# DAU_Kupplung_3phasig_V1_11.net
KiCad netlist of a schematic drawn in EAGLE
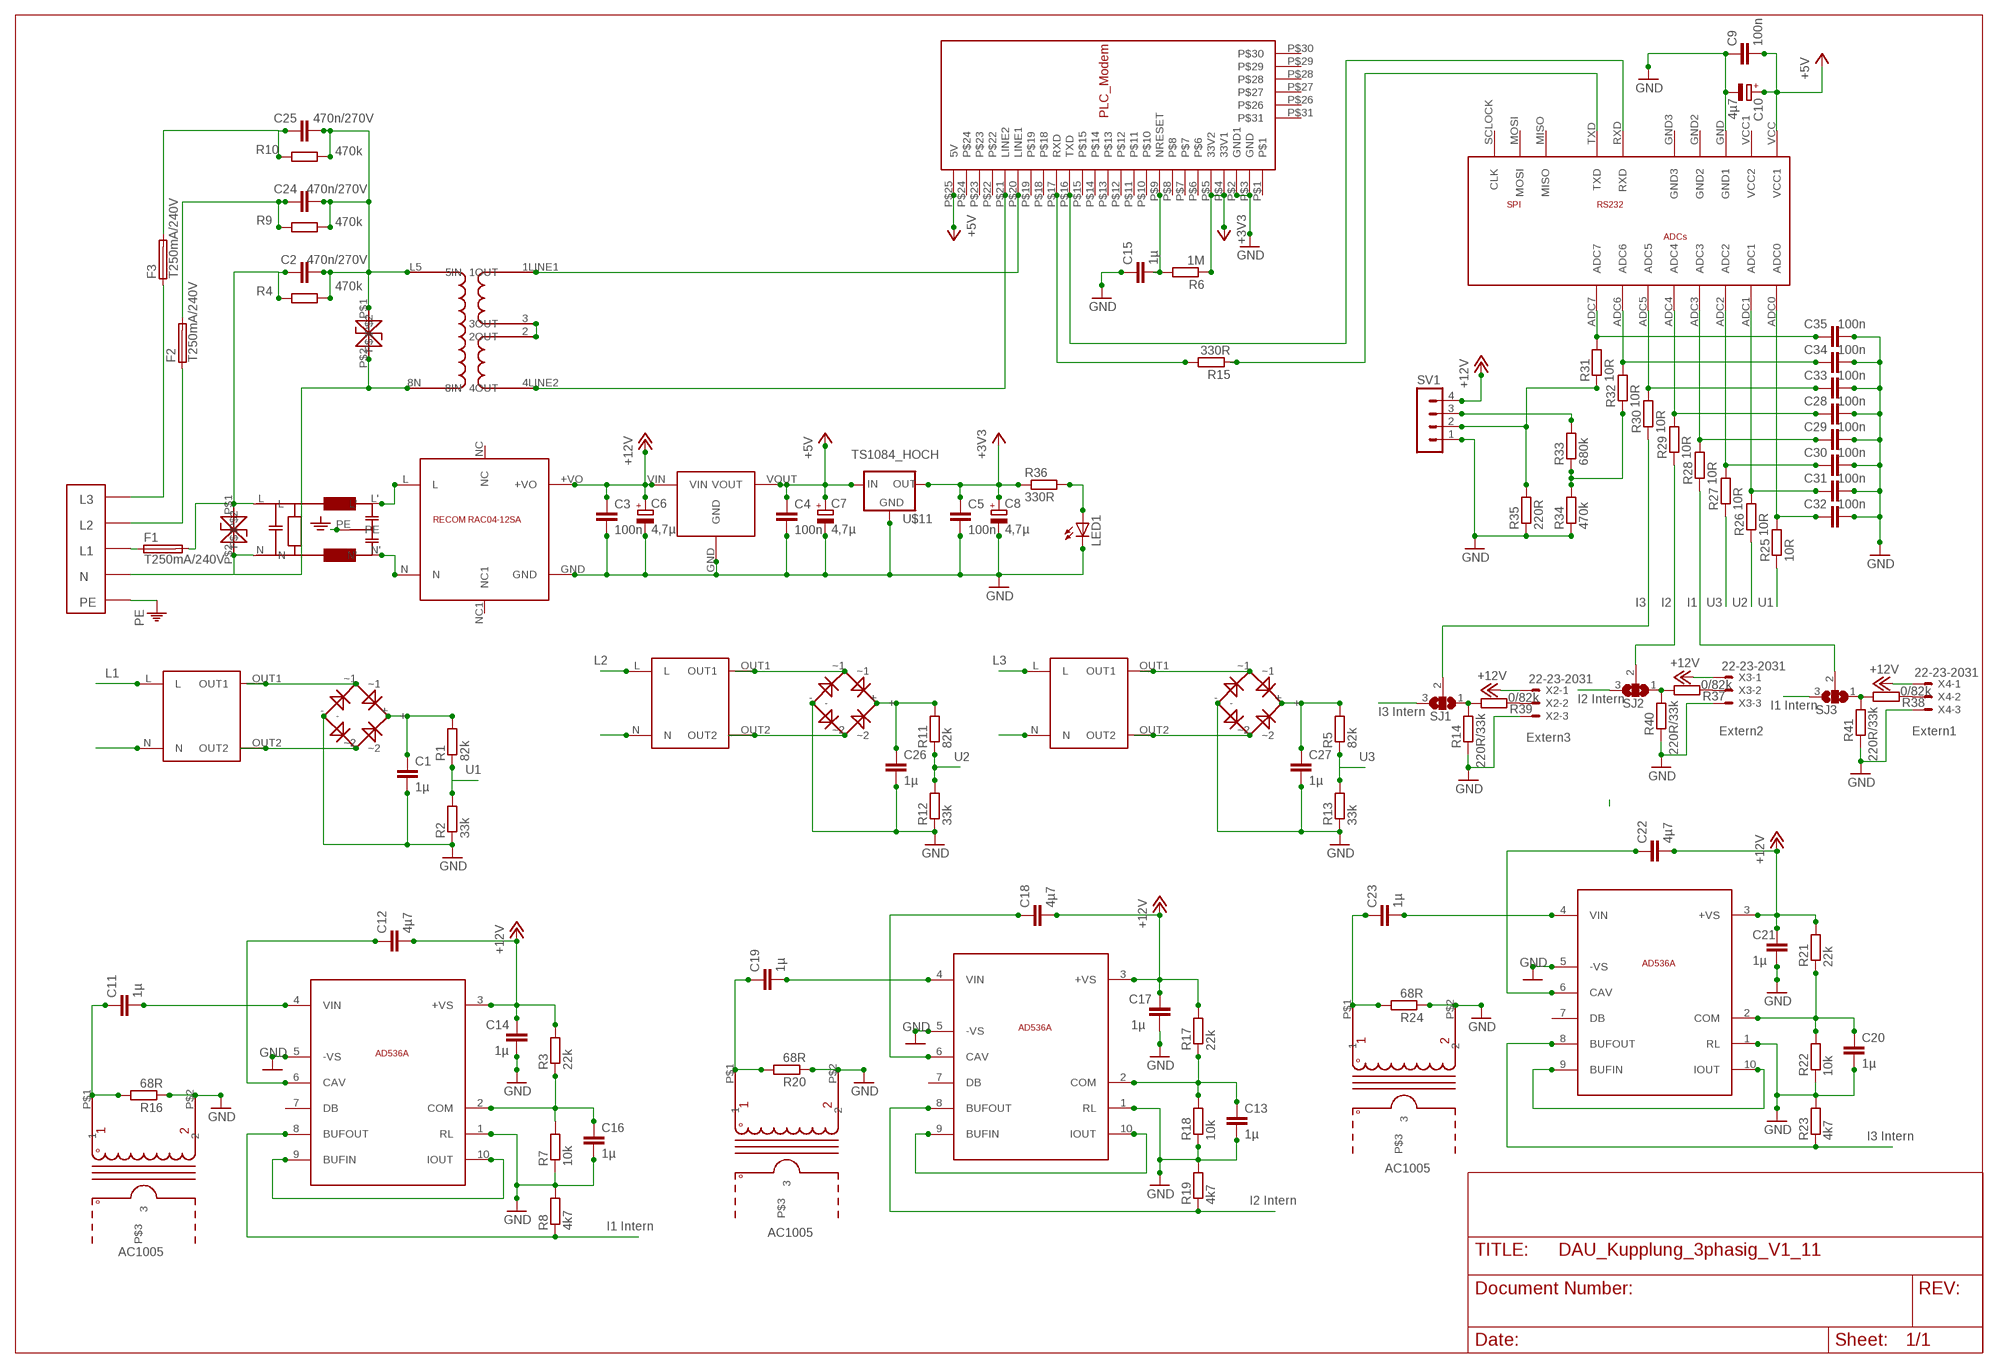
[diagram p0: schematic, sheet 1]

(export (version "E")
  (design (tool "Eeschema 10.0.6"))
  (components
    (comp (ref "AC1002_1")
      (value "AC1010")
      (footprint "eagle-import:AC1010")
      (libsource (lib "eagle-import") (part "AC1010"))
    )
    (comp (ref "C1")
      (value "1µ")
      (footprint "eagle-import:C0805K")
      (libsource (lib "eagle-import") (part "C-EUC0805K"))
    )
    (comp (ref "C2")
      (value "470n/270V")
      (footprint "eagle-import:C225-087X268")
      (libsource (lib "eagle-import") (part "C-EU225-087X268"))
    )
    (comp (ref "C3")
      (value "100n")
      (footprint "eagle-import:C0805K")
      (libsource (lib "eagle-import") (part "C-EUC0805K"))
    )
    (comp (ref "C4")
      (value "100n")
      (footprint "eagle-import:C0805K")
      (libsource (lib "eagle-import") (part "C-EUC0805K"))
    )
    (comp (ref "C5")
      (value "100n")
      (footprint "eagle-import:C0805K")
      (libsource (lib "eagle-import") (part "C-EUC0805K"))
    )
    (comp (ref "C6")
      (value "4,7µ")
      (footprint "eagle-import:E2,5-6")
      (libsource (lib "eagle-import") (part "resistor_CPOL-EUE2.5-6"))
    )
    (comp (ref "C7")
      (value "4,7µ")
      (footprint "eagle-import:E2,5-6")
      (libsource (lib "eagle-import") (part "resistor_CPOL-EUE2.5-6"))
    )
    (comp (ref "C8")
      (value "4,7µ")
      (footprint "eagle-import:E2,5-6")
      (libsource (lib "eagle-import") (part "resistor_CPOL-EUE2.5-6"))
    )
    (comp (ref "C9")
      (value "100n")
      (footprint "eagle-import:C0805K")
      (libsource (lib "eagle-import") (part "C-EUC0805K"))
    )
    (comp (ref "C10")
      (value "4µ7")
      (footprint "eagle-import:E2,5-6E")
      (libsource (lib "eagle-import") (part "CPOL-EUE2,5-6E"))
    )
    (comp (ref "C11")
      (value "1µ")
      (footprint "eagle-import:C0805K")
      (libsource (lib "eagle-import") (part "C-EUC0805K"))
    )
    (comp (ref "C12")
      (value "4µ7")
      (footprint "eagle-import:C0805K")
      (libsource (lib "eagle-import") (part "C-EUC0805K"))
    )
    (comp (ref "C13")
      (value "1µ")
      (footprint "eagle-import:C0805K")
      (libsource (lib "eagle-import") (part "C-EUC0805K"))
    )
    (comp (ref "C14")
      (value "1µ")
      (footprint "eagle-import:C0805K")
      (libsource (lib "eagle-import") (part "C-EUC0805K"))
    )
    (comp (ref "C15")
      (value "1µ")
      (footprint "eagle-import:C0805K")
      (libsource (lib "eagle-import") (part "C-EUC0805K"))
    )
    (comp (ref "C16")
      (value "1µ")
      (footprint "eagle-import:C0805K")
      (libsource (lib "eagle-import") (part "C-EUC0805K"))
    )
    (comp (ref "C17")
      (value "1µ")
      (footprint "eagle-import:C0805K")
      (libsource (lib "eagle-import") (part "C-EUC0805K"))
    )
    (comp (ref "C18")
      (value "4µ7")
      (footprint "eagle-import:C0805K")
      (libsource (lib "eagle-import") (part "C-EUC0805K"))
    )
    (comp (ref "C19")
      (value "1µ")
      (footprint "eagle-import:C0805K")
      (libsource (lib "eagle-import") (part "C-EUC0805K"))
    )
    (comp (ref "C20")
      (value "1µ")
      (footprint "eagle-import:C0805K")
      (libsource (lib "eagle-import") (part "C-EUC0805K"))
    )
    (comp (ref "C21")
      (value "1µ")
      (footprint "eagle-import:C0805K")
      (libsource (lib "eagle-import") (part "C-EUC0805K"))
    )
    (comp (ref "C22")
      (value "4µ7")
      (footprint "eagle-import:C0805K")
      (libsource (lib "eagle-import") (part "C-EUC0805K"))
    )
    (comp (ref "C23")
      (value "1µ")
      (footprint "eagle-import:C0805K")
      (libsource (lib "eagle-import") (part "C-EUC0805K"))
    )
    (comp (ref "C24")
      (value "470n/270V")
      (footprint "eagle-import:C225-087X268")
      (libsource (lib "eagle-import") (part "C-EU225-087X268"))
    )
    (comp (ref "C25")
      (value "470n/270V")
      (footprint "eagle-import:C225-087X268")
      (libsource (lib "eagle-import") (part "C-EU225-087X268"))
    )
    (comp (ref "C26")
      (value "1µ")
      (footprint "eagle-import:C0805K")
      (libsource (lib "eagle-import") (part "C-EUC0805K"))
    )
    (comp (ref "C27")
      (value "1µ")
      (footprint "eagle-import:C0805K")
      (libsource (lib "eagle-import") (part "C-EUC0805K"))
    )
    (comp (ref "C28")
      (value "100n")
      (footprint "eagle-import:C0805K")
      (libsource (lib "eagle-import") (part "C-EUC0805K"))
    )
    (comp (ref "C29")
      (value "100n")
      (footprint "eagle-import:C0805K")
      (libsource (lib "eagle-import") (part "C-EUC0805K"))
    )
    (comp (ref "C30")
      (value "100n")
      (footprint "eagle-import:C0805K")
      (libsource (lib "eagle-import") (part "C-EUC0805K"))
    )
    (comp (ref "C31")
      (value "100n")
      (footprint "eagle-import:C0805K")
      (libsource (lib "eagle-import") (part "C-EUC0805K"))
    )
    (comp (ref "C32")
      (value "100n")
      (footprint "eagle-import:C0805K")
      (libsource (lib "eagle-import") (part "C-EUC0805K"))
    )
    (comp (ref "C33")
      (value "100n")
      (footprint "eagle-import:C0805K")
      (libsource (lib "eagle-import") (part "C-EUC0805K"))
    )
    (comp (ref "C34")
      (value "100n")
      (footprint "eagle-import:C0805K")
      (libsource (lib "eagle-import") (part "C-EUC0805K"))
    )
    (comp (ref "C35")
      (value "100n")
      (footprint "eagle-import:C0805K")
      (libsource (lib "eagle-import") (part "C-EUC0805K"))
    )
    (comp (ref "F1")
      (value "T250mA/240V")
      (footprint "eagle-import:TR5")
      (libsource (lib "eagle-import") (part "TR5"))
    )
    (comp (ref "F2")
      (value "T250mA/240V")
      (footprint "eagle-import:TR5")
      (fields (field (name "OC_FARNELL") "unknown") (field (name "OC_NEWARK") "unknown"))
      (libsource (lib "eagle-import") (part "TR5"))
    )
    (comp (ref "F3")
      (value "T250mA/240V")
      (footprint "eagle-import:TR5")
      (fields (field (name "OC_FARNELL") "unknown") (field (name "OC_NEWARK") "unknown"))
      (libsource (lib "eagle-import") (part "TR5"))
    )
    (comp (ref "LED1")
      (value "LEDSQR2X5")
      (footprint "eagle-import:LED2X5")
      (libsource (lib "eagle-import") (part "LEDSQR2X5"))
    )
    (comp (ref "P6KE300CA")
      (value "P6KE300CA")
      (footprint "eagle-import:TSV")
      (libsource (lib "eagle-import") (part "TSV"))
    )
    (comp (ref "R1")
      (value "82k")
      (footprint "eagle-import:R0805")
      (libsource (lib "eagle-import") (part "R-EU_R0805"))
    )
    (comp (ref "R2")
      (value "33k")
      (footprint "eagle-import:R0805")
      (libsource (lib "eagle-import") (part "R-EU_R0805"))
    )
    (comp (ref "R3")
      (value "22k")
      (footprint "eagle-import:R0805")
      (libsource (lib "eagle-import") (part "R-EU_R0805"))
    )
    (comp (ref "R4")
      (value "470k")
      (footprint "eagle-import:0204_7")
      (libsource (lib "eagle-import") (part "R-EU_0204/7"))
    )
    (comp (ref "R5")
      (value "82k")
      (footprint "eagle-import:R0805")
      (libsource (lib "eagle-import") (part "R-EU_R0805"))
    )
    (comp (ref "R6")
      (value "1M")
      (footprint "eagle-import:R0805")
      (libsource (lib "eagle-import") (part "R-EU_R0805"))
    )
    (comp (ref "R7")
      (value "10k")
      (footprint "eagle-import:R0805")
      (libsource (lib "eagle-import") (part "R-EU_R0805"))
    )
    (comp (ref "R8")
      (value "4k7")
      (footprint "eagle-import:R0805")
      (libsource (lib "eagle-import") (part "R-EU_R0805"))
    )
    (comp (ref "R9")
      (value "470k")
      (footprint "eagle-import:0204_7")
      (libsource (lib "eagle-import") (part "R-EU_0204/7"))
    )
    (comp (ref "R10")
      (value "470k")
      (footprint "eagle-import:0204_7")
      (libsource (lib "eagle-import") (part "R-EU_0204/7"))
    )
    (comp (ref "R11")
      (value "82k")
      (footprint "eagle-import:R0805")
      (libsource (lib "eagle-import") (part "R-EU_R0805"))
    )
    (comp (ref "R12")
      (value "33k")
      (footprint "eagle-import:R0805")
      (libsource (lib "eagle-import") (part "R-EU_R0805"))
    )
    (comp (ref "R13")
      (value "33k")
      (footprint "eagle-import:R0805")
      (libsource (lib "eagle-import") (part "R-EU_R0805"))
    )
    (comp (ref "R14")
      (value "220R/33k")
      (footprint "eagle-import:R0805")
      (libsource (lib "eagle-import") (part "R-EU_R0805"))
    )
    (comp (ref "R15")
      (value "330R")
      (footprint "eagle-import:R0805")
      (libsource (lib "eagle-import") (part "R-EU_R0805"))
    )
    (comp (ref "R16")
      (value "68R")
      (footprint "eagle-import:0204_7")
      (libsource (lib "eagle-import") (part "R-EU_0204/7"))
    )
    (comp (ref "R17")
      (value "22k")
      (footprint "eagle-import:R0805")
      (libsource (lib "eagle-import") (part "R-EU_R0805"))
    )
    (comp (ref "R18")
      (value "10k")
      (footprint "eagle-import:R0805")
      (libsource (lib "eagle-import") (part "R-EU_R0805"))
    )
    (comp (ref "R19")
      (value "4k7")
      (footprint "eagle-import:R0805")
      (libsource (lib "eagle-import") (part "R-EU_R0805"))
    )
    (comp (ref "R20")
      (value "68R")
      (footprint "eagle-import:0204_7")
      (libsource (lib "eagle-import") (part "R-EU_0204/7"))
    )
    (comp (ref "R21")
      (value "22k")
      (footprint "eagle-import:R0805")
      (libsource (lib "eagle-import") (part "R-EU_R0805"))
    )
    (comp (ref "R22")
      (value "10k")
      (footprint "eagle-import:R0805")
      (libsource (lib "eagle-import") (part "R-EU_R0805"))
    )
    (comp (ref "R23")
      (value "4k7")
      (footprint "eagle-import:R0805")
      (libsource (lib "eagle-import") (part "R-EU_R0805"))
    )
    (comp (ref "R24")
      (value "68R")
      (footprint "eagle-import:0204_7")
      (libsource (lib "eagle-import") (part "R-EU_0204/7"))
    )
    (comp (ref "R25")
      (value "10R")
      (footprint "eagle-import:R0805")
      (libsource (lib "eagle-import") (part "R-EU_R0805"))
    )
    (comp (ref "R26")
      (value "10R")
      (footprint "eagle-import:R0805")
      (libsource (lib "eagle-import") (part "R-EU_R0805"))
    )
    (comp (ref "R27")
      (value "10R")
      (footprint "eagle-import:R0805")
      (libsource (lib "eagle-import") (part "R-EU_R0805"))
    )
    (comp (ref "R28")
      (value "10R")
      (footprint "eagle-import:R0805")
      (libsource (lib "eagle-import") (part "R-EU_R0805"))
    )
    (comp (ref "R29")
      (value "10R")
      (footprint "eagle-import:R0805")
      (libsource (lib "eagle-import") (part "R-EU_R0805"))
    )
    (comp (ref "R30")
      (value "10R")
      (footprint "eagle-import:R0805")
      (libsource (lib "eagle-import") (part "R-EU_R0805"))
    )
    (comp (ref "R31")
      (value "10R")
      (footprint "eagle-import:R0805")
      (libsource (lib "eagle-import") (part "R-EU_R0805"))
    )
    (comp (ref "R32")
      (value "10R")
      (footprint "eagle-import:R0805")
      (libsource (lib "eagle-import") (part "R-EU_R0805"))
    )
    (comp (ref "R33")
      (value "680k")
      (footprint "eagle-import:R0805")
      (libsource (lib "eagle-import") (part "R-EU_R0805"))
    )
    (comp (ref "R34")
      (value "470k")
      (footprint "eagle-import:R0805")
      (libsource (lib "eagle-import") (part "R-EU_R0805"))
    )
    (comp (ref "R35")
      (value "220R")
      (footprint "eagle-import:R0805")
      (libsource (lib "eagle-import") (part "R-EU_R0805"))
    )
    (comp (ref "R36")
      (value "330R")
      (footprint "eagle-import:R0805")
      (libsource (lib "eagle-import") (part "R-EU_R0805"))
    )
    (comp (ref "R37")
      (value "0/82k")
      (footprint "eagle-import:R0805")
      (libsource (lib "eagle-import") (part "R-EU_R0805"))
    )
    (comp (ref "R38")
      (value "0/82k")
      (footprint "eagle-import:R0805")
      (libsource (lib "eagle-import") (part "R-EU_R0805"))
    )
    (comp (ref "R39")
      (value "0/82k")
      (footprint "eagle-import:R0805")
      (libsource (lib "eagle-import") (part "R-EU_R0805"))
    )
    (comp (ref "R40")
      (value "220R/33k")
      (footprint "eagle-import:R0805")
      (libsource (lib "eagle-import") (part "R-EU_R0805"))
    )
    (comp (ref "R41")
      (value "220R/33k")
      (footprint "eagle-import:R0805")
      (libsource (lib "eagle-import") (part "R-EU_R0805"))
    )
    (comp (ref "SJ1")
      (value "SJ2WW")
      (footprint "eagle-import:SJ_2W")
      (libsource (lib "eagle-import") (part "SJ2WW"))
    )
    (comp (ref "SJ2")
      (value "SJ2WW")
      (footprint "eagle-import:SJ_2W")
      (libsource (lib "eagle-import") (part "SJ2WW"))
    )
    (comp (ref "SJ3")
      (value "SJ2WW")
      (footprint "eagle-import:SJ_2W")
      (libsource (lib "eagle-import") (part "SJ2WW"))
    )
    (comp (ref "SV1")
      (value "MA04-1")
      (footprint "eagle-import:MA04-1")
      (libsource (lib "eagle-import") (part "MA04-1"))
    )
    (comp (ref "TSV2")
      (value "TSV")
      (footprint "eagle-import:TSV")
      (libsource (lib "eagle-import") (part "TSV"))
    )
    (comp (ref "U$1")
      (value "RECOM_RAC04_12SA")
      (footprint "eagle-import:RAC04_12SA")
      (libsource (lib "eagle-import") (part "RECOM_RAC04_12SA"))
    )
    (comp (ref "U$2")
      (value "SICHERHEITSTRAFO")
      (footprint "eagle-import:TRAFO_0,35VA")
      (libsource (lib "eagle-import") (part "SICHERHEITSTRAFO"))
    )
    (comp (ref "U$3")
      (value "ADUC831_MINIMUM")
      (footprint "eagle-import:ADUC_MINIMUM")
      (libsource (lib "eagle-import") (part "ADUC831_MINIMUM"))
    )
    (comp (ref "U$4")
      (value "MODEMSTECKER")
      (footprint "eagle-import:MODEM_FUSS")
      (libsource (lib "eagle-import") (part "MODEMSTECKER"))
    )
    (comp (ref "U$5")
      (value "PLC_UEBERTRAGER_V2")
      (footprint "eagle-import:PLC-UEBERTRAGER_V2")
      (libsource (lib "eagle-import") (part "PLC_UEBERTRAGER_V2"))
    )
    (comp (ref "U$7")
      (value "AC1010")
      (footprint "eagle-import:AC1010")
      (libsource (lib "eagle-import") (part "AC1010"))
    )
    (comp (ref "U$8")
      (value "RECTIFIER")
      (footprint "eagle-import:RECTIFIER")
      (libsource (lib "eagle-import") (part "RECTIFIER"))
    )
    (comp (ref "U$10")
      (value "RECOM_785_05")
      (footprint "eagle-import:RECOM785X")
      (libsource (lib "eagle-import") (part "RECOM_785_05"))
    )
    (comp (ref "U$11")
      (value "TS1084_HOCH")
      (footprint "eagle-import:TS1084_HOCH")
      (libsource (lib "eagle-import") (part "TS1084_HOCH"))
    )
    (comp (ref "U$12")
      (value "AD536")
      (footprint "eagle-import:TO100_10PIN")
      (libsource (lib "eagle-import") (part "AD536"))
    )
    (comp (ref "U$13")
      (value "AD536")
      (footprint "eagle-import:TO100_10PIN")
      (libsource (lib "eagle-import") (part "AD536"))
    )
    (comp (ref "U$14")
      (value "AC1010")
      (footprint "eagle-import:AC1010")
      (libsource (lib "eagle-import") (part "AC1010"))
    )
    (comp (ref "U$15")
      (value "AD536")
      (footprint "eagle-import:TO100_10PIN")
      (libsource (lib "eagle-import") (part "AD536"))
    )
    (comp (ref "U$16")
      (value "SICHERHEITSTRAFO")
      (footprint "eagle-import:TRAFO_0,35VA")
      (libsource (lib "eagle-import") (part "SICHERHEITSTRAFO"))
    )
    (comp (ref "U$17")
      (value "RECTIFIER")
      (footprint "eagle-import:RECTIFIER")
      (libsource (lib "eagle-import") (part "RECTIFIER"))
    )
    (comp (ref "U$18")
      (value "SICHERHEITSTRAFO")
      (footprint "eagle-import:TRAFO_0,35VA")
      (libsource (lib "eagle-import") (part "SICHERHEITSTRAFO"))
    )
    (comp (ref "U$19")
      (value "RECTIFIER")
      (footprint "eagle-import:RECTIFIER")
      (libsource (lib "eagle-import") (part "RECTIFIER"))
    )
    (comp (ref "U$20")
      (value "NETZFILTER_05_A")
      (footprint "eagle-import:NETZFILTER")
      (libsource (lib "eagle-import") (part "NETZFILTER_05_A"))
    )
    (comp (ref "X1")
      (value "CONNECTO_5_POL")
      (footprint "eagle-import:CONNECTOR_5_POL")
      (libsource (lib "eagle-import") (part "CONNECTO_5_POL"))
    )
    (comp (ref "X2")
      (value "22-23-2031")
      (footprint "eagle-import:22-23-2031")
      (fields (field (name "MF") "MOLEX"))
      (libsource (lib "eagle-import") (part "22-23-2031"))
    )
    (comp (ref "X3")
      (value "22-23-2031")
      (footprint "eagle-import:22-23-2031")
      (fields (field (name "MF") "MOLEX"))
      (libsource (lib "eagle-import") (part "22-23-2031"))
    )
    (comp (ref "X4")
      (value "22-23-2031")
      (footprint "eagle-import:22-23-2031")
      (fields (field (name "MF") "MOLEX"))
      (libsource (lib "eagle-import") (part "22-23-2031"))
    )
  )
  (nets
    (net (code "1") (name "+3V3") (class "Default")
      (node (ref "C5") (pin "1") (pinfunction "1_1") (pintype "passive"))
      (node (ref "C8") (pin "+") (pinfunction "+_+") (pintype "passive"))
      (node (ref "R36") (pin "1") (pinfunction "1_1") (pintype "passive"))
      (node (ref "R6") (pin "1") (pinfunction "1_1") (pintype "passive"))
      (node (ref "U$11") (pin "OUT") (pinfunction "OUT_OUT") (pintype "passive"))
      (node (ref "U$4") (pin "P$4") (pinfunction "33V1_P$4") (pintype "bidirectional"))
      (node (ref "U$4") (pin "P$5") (pinfunction "33V2_P$5") (pintype "bidirectional"))
    )
    (net (code "2") (name "+5V") (class "Default")
      (node (ref "C10") (pin "+") (pinfunction "+_+") (pintype "passive"))
      (node (ref "C4") (pin "1") (pinfunction "1_1") (pintype "passive"))
      (node (ref "C7") (pin "+") (pinfunction "+_+") (pintype "passive"))
      (node (ref "C9") (pin "2") (pinfunction "2_2") (pintype "passive"))
      (node (ref "U$10") (pin "VOUT") (pinfunction "VOUT_VOUT") (pintype "bidirectional"))
      (node (ref "U$11") (pin "IN") (pinfunction "IN_IN") (pintype "input"))
      (node (ref "U$3") (pin "VCC") (pinfunction "VCC1_VCC") (pintype "bidirectional"))
      (node (ref "U$4") (pin "P$25") (pinfunction "5V_P$25") (pintype "bidirectional"))
    )
    (net (code "3") (name "+12V") (class "Default")
      (node (ref "C12") (pin "2") (pinfunction "2_2") (pintype "passive"))
      (node (ref "C14") (pin "2") (pinfunction "2_2") (pintype "passive"))
      (node (ref "C17") (pin "2") (pinfunction "2_2") (pintype "passive"))
      (node (ref "C18") (pin "2") (pinfunction "2_2") (pintype "passive"))
      (node (ref "C21") (pin "1") (pinfunction "1_1") (pintype "passive"))
      (node (ref "C22") (pin "2") (pinfunction "2_2") (pintype "passive"))
      (node (ref "C3") (pin "1") (pinfunction "1_1") (pintype "passive"))
      (node (ref "C6") (pin "+") (pinfunction "+_+") (pintype "passive"))
      (node (ref "R17") (pin "2") (pinfunction "2_2") (pintype "passive"))
      (node (ref "R21") (pin "2") (pinfunction "2_2") (pintype "passive"))
      (node (ref "R3") (pin "2") (pinfunction "2_2") (pintype "passive"))
      (node (ref "SV1") (pin "4") (pinfunction "4_4") (pintype "passive"))
      (node (ref "U$1") (pin "+VO") (pinfunction "+VO_+VO") (pintype "bidirectional"))
      (node (ref "U$10") (pin "VIN") (pinfunction "VIN_VIN") (pintype "bidirectional"))
      (node (ref "U$12") (pin "3") (pinfunction "+VS_3") (pintype "bidirectional"))
      (node (ref "U$13") (pin "3") (pinfunction "+VS_3") (pintype "bidirectional"))
      (node (ref "U$15") (pin "3") (pinfunction "+VS_3") (pintype "bidirectional"))
      (node (ref "X2") (pin "1") (pinfunction "S_1") (pintype "passive"))
      (node (ref "X3") (pin "1") (pinfunction "S_1") (pintype "passive"))
      (node (ref "X4") (pin "1") (pinfunction "S_1") (pintype "passive"))
    )
    (net (code "4") (name "/I1INTERN") (class "Default")
      (node (ref "R8") (pin "1") (pinfunction "1_1") (pintype "passive"))
      (node (ref "SJ3") (pin "3") (pinfunction "3_3") (pintype "passive"))
      (node (ref "U$13") (pin "8") (pinfunction "BUFOUT_8") (pintype "bidirectional"))
    )
    (net (code "5") (name "/I2INTERN") (class "Default")
      (node (ref "R19") (pin "1") (pinfunction "1_1") (pintype "passive"))
      (node (ref "SJ2") (pin "3") (pinfunction "3_3") (pintype "passive"))
      (node (ref "U$12") (pin "8") (pinfunction "BUFOUT_8") (pintype "bidirectional"))
    )
    (net (code "6") (name "/I3INTERN") (class "Default")
      (node (ref "R23") (pin "1") (pinfunction "1_1") (pintype "passive"))
      (node (ref "SJ1") (pin "3") (pinfunction "3_3") (pintype "passive"))
      (node (ref "U$15") (pin "8") (pinfunction "BUFOUT_8") (pintype "bidirectional"))
    )
    (net (code "7") (name "/L1") (class "Default")
      (node (ref "C2") (pin "1") (pinfunction "1_1") (pintype "passive"))
      (node (ref "F1") (pin "2") (pinfunction "2_2") (pintype "passive"))
      (node (ref "P6KE300CA") (pin "P$1") (pinfunction "P$1_P$1") (pintype "bidirectional"))
      (node (ref "R4") (pin "2") (pinfunction "2_2") (pintype "passive"))
      (node (ref "U$2") (pin "L") (pinfunction "L_L") (pintype "bidirectional"))
      (node (ref "U$20") (pin "L") (pinfunction "L_L") (pintype "bidirectional"))
    )
    (net (code "8") (name "/L2") (class "Default")
      (node (ref "C24") (pin "1") (pinfunction "1_1") (pintype "passive"))
      (node (ref "F2") (pin "2") (pinfunction "2_2") (pintype "passive"))
      (node (ref "R9") (pin "2") (pinfunction "2_2") (pintype "passive"))
      (node (ref "U$16") (pin "L") (pinfunction "L_L") (pintype "bidirectional"))
    )
    (net (code "9") (name "/L3") (class "Default")
      (node (ref "C25") (pin "1") (pinfunction "1_1") (pintype "passive"))
      (node (ref "F3") (pin "2") (pinfunction "2_2") (pintype "passive"))
      (node (ref "R10") (pin "2") (pinfunction "2_2") (pintype "passive"))
      (node (ref "U$18") (pin "L") (pinfunction "L_L") (pintype "bidirectional"))
    )
    (net (code "10") (name "/N") (class "Default")
      (node (ref "P6KE300CA") (pin "P$2") (pinfunction "P$2_P$2") (pintype "bidirectional"))
      (node (ref "TSV2") (pin "P$2") (pinfunction "P$2_P$2") (pintype "bidirectional"))
      (node (ref "U$16") (pin "N") (pinfunction "N_N") (pintype "bidirectional"))
      (node (ref "U$18") (pin "N") (pinfunction "N_N") (pintype "bidirectional"))
      (node (ref "U$2") (pin "N") (pinfunction "N_N") (pintype "bidirectional"))
      (node (ref "U$20") (pin "N") (pinfunction "N_N") (pintype "bidirectional"))
      (node (ref "U$5") (pin "8N") (pinfunction "8IN_8N") (pintype "input"))
      (node (ref "X1") (pin "P$4") (pinfunction "P$4_P$4") (pintype "bidirectional"))
    )
    (net (code "11") (name "/U1") (class "Default")
      (node (ref "R1") (pin "1") (pinfunction "1_1") (pintype "passive"))
      (node (ref "R2") (pin "2") (pinfunction "2_2") (pintype "passive"))
      (node (ref "R25") (pin "1") (pinfunction "1_1") (pintype "passive"))
    )
    (net (code "12") (name "/U2") (class "Default")
      (node (ref "R11") (pin "1") (pinfunction "1_1") (pintype "passive"))
      (node (ref "R12") (pin "2") (pinfunction "2_2") (pintype "passive"))
      (node (ref "R26") (pin "1") (pinfunction "1_1") (pintype "passive"))
    )
    (net (code "13") (name "/U3") (class "Default")
      (node (ref "R13") (pin "2") (pinfunction "2_2") (pintype "passive"))
      (node (ref "R27") (pin "1") (pinfunction "1_1") (pintype "passive"))
      (node (ref "R5") (pin "1") (pinfunction "1_1") (pintype "passive"))
    )
    (net (code "14") (name "GND") (class "Default")
      (node (ref "AC1002_1") (pin "P$2") (pinfunction "2_P$2") (pintype "output"))
      (node (ref "C1") (pin "2") (pinfunction "2_2") (pintype "passive"))
      (node (ref "C10") (pin "-") (pinfunction "-_-") (pintype "passive"))
      (node (ref "C13") (pin "2") (pinfunction "2_2") (pintype "passive"))
      (node (ref "C14") (pin "1") (pinfunction "1_1") (pintype "passive"))
      (node (ref "C15") (pin "1") (pinfunction "1_1") (pintype "passive"))
      (node (ref "C16") (pin "2") (pinfunction "2_2") (pintype "passive"))
      (node (ref "C17") (pin "1") (pinfunction "1_1") (pintype "passive"))
      (node (ref "C20") (pin "2") (pinfunction "2_2") (pintype "passive"))
      (node (ref "C21") (pin "2") (pinfunction "2_2") (pintype "passive"))
      (node (ref "C26") (pin "2") (pinfunction "2_2") (pintype "passive"))
      (node (ref "C27") (pin "2") (pinfunction "2_2") (pintype "passive"))
      (node (ref "C28") (pin "2") (pinfunction "2_2") (pintype "passive"))
      (node (ref "C29") (pin "2") (pinfunction "2_2") (pintype "passive"))
      (node (ref "C3") (pin "2") (pinfunction "2_2") (pintype "passive"))
      (node (ref "C30") (pin "2") (pinfunction "2_2") (pintype "passive"))
      (node (ref "C31") (pin "2") (pinfunction "2_2") (pintype "passive"))
      (node (ref "C32") (pin "2") (pinfunction "2_2") (pintype "passive"))
      (node (ref "C33") (pin "2") (pinfunction "2_2") (pintype "passive"))
      (node (ref "C34") (pin "2") (pinfunction "2_2") (pintype "passive"))
      (node (ref "C35") (pin "2") (pinfunction "2_2") (pintype "passive"))
      (node (ref "C4") (pin "2") (pinfunction "2_2") (pintype "passive"))
      (node (ref "C5") (pin "2") (pinfunction "2_2") (pintype "passive"))
      (node (ref "C6") (pin "-") (pinfunction "-_-") (pintype "passive"))
      (node (ref "C7") (pin "-") (pinfunction "-_-") (pintype "passive"))
      (node (ref "C8") (pin "-") (pinfunction "-_-") (pintype "passive"))
      (node (ref "C9") (pin "1") (pinfunction "1_1") (pintype "passive"))
      (node (ref "LED1") (pin "K") (pinfunction "C_K") (pintype "passive"))
      (node (ref "R12") (pin "1") (pinfunction "1_1") (pintype "passive"))
      (node (ref "R13") (pin "1") (pinfunction "1_1") (pintype "passive"))
      (node (ref "R14") (pin "1") (pinfunction "1_1") (pintype "passive"))
      (node (ref "R16") (pin "1") (pinfunction "1_1") (pintype "passive"))
      (node (ref "R18") (pin "1") (pinfunction "1_1") (pintype "passive"))
      (node (ref "R19") (pin "2") (pinfunction "2_2") (pintype "passive"))
      (node (ref "R2") (pin "1") (pinfunction "1_1") (pintype "passive"))
      (node (ref "R20") (pin "1") (pinfunction "1_1") (pintype "passive"))
      (node (ref "R22") (pin "1") (pinfunction "1_1") (pintype "passive"))
      (node (ref "R23") (pin "2") (pinfunction "2_2") (pintype "passive"))
      (node (ref "R24") (pin "1") (pinfunction "1_1") (pintype "passive"))
      (node (ref "R34") (pin "1") (pinfunction "1_1") (pintype "passive"))
      (node (ref "R35") (pin "1") (pinfunction "1_1") (pintype "passive"))
      (node (ref "R40") (pin "1") (pinfunction "1_1") (pintype "passive"))
      (node (ref "R41") (pin "1") (pinfunction "1_1") (pintype "passive"))
      (node (ref "R7") (pin "1") (pinfunction "1_1") (pintype "passive"))
      (node (ref "R8") (pin "2") (pinfunction "2_2") (pintype "passive"))
      (node (ref "SV1") (pin "1") (pinfunction "1_1") (pintype "passive"))
      (node (ref "U$1") (pin "GND") (pinfunction "GND_GND") (pintype "bidirectional"))
      (node (ref "U$10") (pin "GND") (pinfunction "GND_GND") (pintype "bidirectional"))
      (node (ref "U$11") (pin "GND") (pinfunction "GND_GND") (pintype "input"))
      (node (ref "U$12") (pin "1") (pinfunction "RL_1") (pintype "bidirectional"))
      (node (ref "U$12") (pin "5") (pinfunction "-VS_5") (pintype "bidirectional"))
      (node (ref "U$13") (pin "1") (pinfunction "RL_1") (pintype "bidirectional"))
      (node (ref "U$13") (pin "5") (pinfunction "-VS_5") (pintype "bidirectional"))
      (node (ref "U$14") (pin "P$2") (pinfunction "2_P$2") (pintype "output"))
      (node (ref "U$15") (pin "1") (pinfunction "RL_1") (pintype "bidirectional"))
      (node (ref "U$15") (pin "5") (pinfunction "-VS_5") (pintype "bidirectional"))
      (node (ref "U$17") (pin "-") (pinfunction "-_-") (pintype "bidirectional"))
      (node (ref "U$19") (pin "-") (pinfunction "-_-") (pintype "bidirectional"))
      (node (ref "U$3") (pin "GND") (pinfunction "GND1_GND") (pintype "bidirectional"))
      (node (ref "U$4") (pin "P$2") (pinfunction "GND1_P$2") (pintype "bidirectional"))
      (node (ref "U$4") (pin "P$3") (pinfunction "GND_P$3") (pintype "bidirectional"))
      (node (ref "U$7") (pin "P$2") (pinfunction "2_P$2") (pintype "output"))
      (node (ref "U$8") (pin "-") (pinfunction "-_-") (pintype "bidirectional"))
      (node (ref "X2") (pin "3") (pinfunction "S_3") (pintype "passive"))
      (node (ref "X3") (pin "3") (pinfunction "S_3") (pintype "passive"))
      (node (ref "X4") (pin "3") (pinfunction "S_3") (pintype "passive"))
    )
    (net (code "15") (name "Net-(AC1002_1-1)") (class "Default")
      (node (ref "AC1002_1") (pin "P$1") (pinfunction "1_P$1") (pintype "output"))
      (node (ref "C11") (pin "1") (pinfunction "1_1") (pintype "passive"))
      (node (ref "R16") (pin "2") (pinfunction "2_2") (pintype "passive"))
    )
    (net (code "16") (name "Net-(C1-Pad1)") (class "Default")
      (node (ref "C1") (pin "1") (pinfunction "1_1") (pintype "passive"))
      (node (ref "R1") (pin "2") (pinfunction "2_2") (pintype "passive"))
      (node (ref "U$8") (pin "+") (pinfunction "+_+") (pintype "bidirectional"))
    )
    (net (code "17") (name "Net-(C26-Pad1)") (class "Default")
      (node (ref "C26") (pin "1") (pinfunction "1_1") (pintype "passive"))
      (node (ref "R11") (pin "2") (pinfunction "2_2") (pintype "passive"))
      (node (ref "U$17") (pin "+") (pinfunction "+_+") (pintype "bidirectional"))
    )
    (net (code "18") (name "Net-(C27-Pad1)") (class "Default")
      (node (ref "C27") (pin "1") (pinfunction "1_1") (pintype "passive"))
      (node (ref "R5") (pin "2") (pinfunction "2_2") (pintype "passive"))
      (node (ref "U$19") (pin "+") (pinfunction "+_+") (pintype "bidirectional"))
    )
    (net (code "19") (name "Net-(C28-Pad1)") (class "Default")
      (node (ref "C28") (pin "1") (pinfunction "1_1") (pintype "passive"))
      (node (ref "R29") (pin "2") (pinfunction "2_2") (pintype "passive"))
      (node (ref "U$3") (pin "ADC4") (pinfunction "ADC4_ADC4") (pintype "bidirectional"))
    )
    (net (code "20") (name "Net-(C29-Pad1)") (class "Default")
      (node (ref "C29") (pin "1") (pinfunction "1_1") (pintype "passive"))
      (node (ref "R28") (pin "2") (pinfunction "2_2") (pintype "passive"))
      (node (ref "U$3") (pin "ADC3") (pinfunction "ADC3_ADC3") (pintype "bidirectional"))
    )
    (net (code "21") (name "Net-(C30-Pad1)") (class "Default")
      (node (ref "C30") (pin "1") (pinfunction "1_1") (pintype "passive"))
      (node (ref "R27") (pin "2") (pinfunction "2_2") (pintype "passive"))
      (node (ref "U$3") (pin "ADC2") (pinfunction "ADC2_ADC2") (pintype "bidirectional"))
    )
    (net (code "22") (name "Net-(C31-Pad1)") (class "Default")
      (node (ref "C31") (pin "1") (pinfunction "1_1") (pintype "passive"))
      (node (ref "R26") (pin "2") (pinfunction "2_2") (pintype "passive"))
      (node (ref "U$3") (pin "ADC1") (pinfunction "ADC1_ADC1") (pintype "bidirectional"))
    )
    (net (code "23") (name "Net-(C32-Pad1)") (class "Default")
      (node (ref "C32") (pin "1") (pinfunction "1_1") (pintype "passive"))
      (node (ref "R25") (pin "2") (pinfunction "2_2") (pintype "passive"))
      (node (ref "U$3") (pin "ADC0") (pinfunction "ADC0_ADC0") (pintype "bidirectional"))
    )
    (net (code "24") (name "Net-(C33-Pad1)") (class "Default")
      (node (ref "C33") (pin "1") (pinfunction "1_1") (pintype "passive"))
      (node (ref "R30") (pin "2") (pinfunction "2_2") (pintype "passive"))
      (node (ref "U$3") (pin "ADC5") (pinfunction "ADC5_ADC5") (pintype "bidirectional"))
    )
    (net (code "25") (name "Net-(C34-Pad1)") (class "Default")
      (node (ref "C34") (pin "1") (pinfunction "1_1") (pintype "passive"))
      (node (ref "R32") (pin "2") (pinfunction "2_2") (pintype "passive"))
      (node (ref "U$3") (pin "ADC6") (pinfunction "ADC6_ADC6") (pintype "bidirectional"))
    )
    (net (code "26") (name "Net-(C35-Pad1)") (class "Default")
      (node (ref "C35") (pin "1") (pinfunction "1_1") (pintype "passive"))
      (node (ref "R31") (pin "2") (pinfunction "2_2") (pintype "passive"))
      (node (ref "U$3") (pin "ADC7") (pinfunction "ADC7_ADC7") (pintype "bidirectional"))
    )
    (net (code "27") (name "Net-(F1-Pad1)") (class "Default")
      (node (ref "F1") (pin "1") (pinfunction "1_1") (pintype "passive"))
      (node (ref "X1") (pin "P$3") (pinfunction "P$3_P$3") (pintype "bidirectional"))
    )
    (net (code "28") (name "Net-(F2-Pad1)") (class "Default")
      (node (ref "F2") (pin "1") (pinfunction "1_1") (pintype "passive"))
      (node (ref "X1") (pin "P$2") (pinfunction "P$2_P$2") (pintype "bidirectional"))
    )
    (net (code "29") (name "Net-(F3-Pad1)") (class "Default")
      (node (ref "F3") (pin "1") (pinfunction "1_1") (pintype "passive"))
      (node (ref "X1") (pin "P$1") (pinfunction "P$1_P$1") (pintype "bidirectional"))
    )
    (net (code "30") (name "Net-(LED1-PadA)") (class "Default")
      (node (ref "LED1") (pin "A") (pinfunction "A_A") (pintype "passive"))
      (node (ref "R36") (pin "2") (pinfunction "2_2") (pintype "passive"))
    )
    (net (code "31") (name "Net-(R14-Pad2)") (class "Default")
      (node (ref "R14") (pin "2") (pinfunction "2_2") (pintype "passive"))
      (node (ref "R39") (pin "2") (pinfunction "2_2") (pintype "passive"))
      (node (ref "SJ1") (pin "1") (pinfunction "1_1") (pintype "passive"))
    )
    (net (code "32") (name "Net-(R15-Pad1)") (class "Default")
      (node (ref "R15") (pin "1") (pinfunction "1_1") (pintype "passive"))
      (node (ref "U$3") (pin "TXD") (pinfunction "TXD_TXD") (pintype "bidirectional"))
    )
    (net (code "33") (name "Net-(R28-Pad1)") (class "Default")
      (node (ref "R28") (pin "1") (pinfunction "1_1") (pintype "passive"))
      (node (ref "SJ3") (pin "2") (pinfunction "2_2") (pintype "passive"))
    )
    (net (code "34") (name "Net-(R29-Pad1)") (class "Default")
      (node (ref "R29") (pin "1") (pinfunction "1_1") (pintype "passive"))
      (node (ref "SJ2") (pin "2") (pinfunction "2_2") (pintype "passive"))
    )
    (net (code "35") (name "Net-(R30-Pad1)") (class "Default")
      (node (ref "R30") (pin "1") (pinfunction "1_1") (pintype "passive"))
      (node (ref "SJ1") (pin "2") (pinfunction "2_2") (pintype "passive"))
    )
    (net (code "36") (name "Net-(R31-Pad1)") (class "Default")
      (node (ref "R31") (pin "1") (pinfunction "1_1") (pintype "passive"))
      (node (ref "R35") (pin "2") (pinfunction "2_2") (pintype "passive"))
      (node (ref "SV1") (pin "2") (pinfunction "2_2") (pintype "passive"))
    )
    (net (code "37") (name "Net-(R32-Pad1)") (class "Default")
      (node (ref "R32") (pin "1") (pinfunction "1_1") (pintype "passive"))
      (node (ref "R33") (pin "1") (pinfunction "1_1") (pintype "passive"))
      (node (ref "R34") (pin "2") (pinfunction "2_2") (pintype "passive"))
    )
    (net (code "38") (name "Net-(R33-Pad2)") (class "Default")
      (node (ref "R33") (pin "2") (pinfunction "2_2") (pintype "passive"))
      (node (ref "SV1") (pin "3") (pinfunction "3_3") (pintype "passive"))
    )
    (net (code "39") (name "Net-(R37-Pad2)") (class "Default")
      (node (ref "R37") (pin "2") (pinfunction "2_2") (pintype "passive"))
      (node (ref "R40") (pin "2") (pinfunction "2_2") (pintype "passive"))
      (node (ref "SJ2") (pin "1") (pinfunction "1_1") (pintype "passive"))
    )
    (net (code "40") (name "Net-(R38-Pad2)") (class "Default")
      (node (ref "R38") (pin "2") (pinfunction "2_2") (pintype "passive"))
      (node (ref "R41") (pin "2") (pinfunction "2_2") (pintype "passive"))
      (node (ref "SJ3") (pin "1") (pinfunction "1_1") (pintype "passive"))
    )
    (net (code "41") (name "Net-(U$1-PadL)") (class "Default")
      (node (ref "U$1") (pin "L") (pinfunction "L_L") (pintype "bidirectional"))
      (node (ref "U$20") (pin "L'") (pinfunction "L'_L'") (pintype "bidirectional"))
    )
    (net (code "42") (name "Net-(U$1-PadN)") (class "Default")
      (node (ref "U$1") (pin "N") (pinfunction "N_N") (pintype "bidirectional"))
      (node (ref "U$20") (pin "N'") (pinfunction "N'_N'") (pintype "bidirectional"))
    )
    (net (code "43") (name "Net-(U$4-LINE1)") (class "Default")
      (node (ref "U$4") (pin "P$20") (pinfunction "LINE1_P$20") (pintype "bidirectional"))
      (node (ref "U$5") (pin "1LINE1") (pinfunction "1OUT_1LINE1") (pintype "output"))
    )
    (net (code "44") (name "Net-(U$4-LINE2)") (class "Default")
      (node (ref "U$4") (pin "P$21") (pinfunction "LINE2_P$21") (pintype "bidirectional"))
      (node (ref "U$5") (pin "4LINE2") (pinfunction "4OUT_4LINE2") (pintype "output"))
    )
    (net (code "45") (name "Net-(U$4-NRESET)") (class "Default")
      (node (ref "C15") (pin "2") (pinfunction "2_2") (pintype "passive"))
      (node (ref "R6") (pin "2") (pinfunction "2_2") (pintype "passive"))
      (node (ref "U$4") (pin "P$9") (pinfunction "NRESET_P$9") (pintype "bidirectional"))
    )
    (net (code "46") (name "Net-(U$4-RXD)") (class "Default")
      (node (ref "R15") (pin "2") (pinfunction "2_2") (pintype "passive"))
      (node (ref "U$4") (pin "P$17") (pinfunction "RXD_P$17") (pintype "bidirectional"))
    )
    (net (code "47") (name "Net-(U$4-TXD)") (class "Default")
      (node (ref "U$3") (pin "RXD") (pinfunction "RXD_RXD") (pintype "bidirectional"))
      (node (ref "U$4") (pin "P$16") (pinfunction "TXD_P$16") (pintype "bidirectional"))
    )
    (net (code "48") (name "Net-(U$5-2OUT)") (class "Default")
      (node (ref "U$5") (pin "2") (pinfunction "2OUT_2") (pintype "output"))
      (node (ref "U$5") (pin "3") (pinfunction "3OUT_3") (pintype "output"))
    )
    (net (code "49") (name "Net-(U$5-5IN)") (class "Default")
      (node (ref "C2") (pin "2") (pinfunction "2_2") (pintype "passive"))
      (node (ref "C24") (pin "2") (pinfunction "2_2") (pintype "passive"))
      (node (ref "C25") (pin "2") (pinfunction "2_2") (pintype "passive"))
      (node (ref "R10") (pin "1") (pinfunction "1_1") (pintype "passive"))
      (node (ref "R4") (pin "1") (pinfunction "1_1") (pintype "passive"))
      (node (ref "R9") (pin "1") (pinfunction "1_1") (pintype "passive"))
      (node (ref "TSV2") (pin "P$1") (pinfunction "P$1_P$1") (pintype "bidirectional"))
      (node (ref "U$5") (pin "L5") (pinfunction "5IN_L5") (pintype "input"))
    )
    (net (code "50") (name "Net-(U$7-1)") (class "Default")
      (node (ref "C19") (pin "1") (pinfunction "1_1") (pintype "passive"))
      (node (ref "R20") (pin "2") (pinfunction "2_2") (pintype "passive"))
      (node (ref "U$7") (pin "P$1") (pinfunction "1_P$1") (pintype "output"))
    )
    (net (code "51") (name "Net-(U$8-~{1})") (class "Default")
      (node (ref "U$2") (pin "OUT1") (pinfunction "OUT1_OUT1") (pintype "bidirectional"))
      (node (ref "U$8") (pin "~1") (pinfunction "~{1}_~1") (pintype "bidirectional"))
    )
    (net (code "52") (name "Net-(U$8-~{2})") (class "Default")
      (node (ref "U$2") (pin "OUT2") (pinfunction "OUT2_OUT2") (pintype "bidirectional"))
      (node (ref "U$8") (pin "~2") (pinfunction "~{2}_~2") (pintype "bidirectional"))
    )
    (net (code "53") (name "Net-(U$12-BUFIN)") (class "Default")
      (node (ref "U$12") (pin "10") (pinfunction "IOUT_10") (pintype "bidirectional"))
      (node (ref "U$12") (pin "9") (pinfunction "BUFIN_9") (pintype "bidirectional"))
    )
    (net (code "54") (name "Net-(U$12-CAV)") (class "Default")
      (node (ref "C18") (pin "1") (pinfunction "1_1") (pintype "passive"))
      (node (ref "U$12") (pin "6") (pinfunction "CAV_6") (pintype "bidirectional"))
    )
    (net (code "55") (name "Net-(U$12-COM)") (class "Default")
      (node (ref "C13") (pin "1") (pinfunction "1_1") (pintype "passive"))
      (node (ref "R17") (pin "1") (pinfunction "1_1") (pintype "passive"))
      (node (ref "R18") (pin "2") (pinfunction "2_2") (pintype "passive"))
      (node (ref "U$12") (pin "2") (pinfunction "COM_2") (pintype "bidirectional"))
    )
    (net (code "56") (name "Net-(U$12-VIN)") (class "Default")
      (node (ref "C19") (pin "2") (pinfunction "2_2") (pintype "passive"))
      (node (ref "U$12") (pin "4") (pinfunction "VIN_4") (pintype "bidirectional"))
    )
    (net (code "57") (name "Net-(U$13-BUFIN)") (class "Default")
      (node (ref "U$13") (pin "10") (pinfunction "IOUT_10") (pintype "bidirectional"))
      (node (ref "U$13") (pin "9") (pinfunction "BUFIN_9") (pintype "bidirectional"))
    )
    (net (code "58") (name "Net-(U$13-CAV)") (class "Default")
      (node (ref "C12") (pin "1") (pinfunction "1_1") (pintype "passive"))
      (node (ref "U$13") (pin "6") (pinfunction "CAV_6") (pintype "bidirectional"))
    )
    (net (code "59") (name "Net-(U$13-COM)") (class "Default")
      (node (ref "C16") (pin "1") (pinfunction "1_1") (pintype "passive"))
      (node (ref "R3") (pin "1") (pinfunction "1_1") (pintype "passive"))
      (node (ref "R7") (pin "2") (pinfunction "2_2") (pintype "passive"))
      (node (ref "U$13") (pin "2") (pinfunction "COM_2") (pintype "bidirectional"))
    )
    (net (code "60") (name "Net-(U$13-VIN)") (class "Default")
      (node (ref "C11") (pin "2") (pinfunction "2_2") (pintype "passive"))
      (node (ref "U$13") (pin "4") (pinfunction "VIN_4") (pintype "bidirectional"))
    )
    (net (code "61") (name "Net-(U$14-1)") (class "Default")
      (node (ref "C23") (pin "1") (pinfunction "1_1") (pintype "passive"))
      (node (ref "R24") (pin "2") (pinfunction "2_2") (pintype "passive"))
      (node (ref "U$14") (pin "P$1") (pinfunction "1_P$1") (pintype "output"))
    )
    (net (code "62") (name "Net-(U$15-BUFIN)") (class "Default")
      (node (ref "U$15") (pin "10") (pinfunction "IOUT_10") (pintype "bidirectional"))
      (node (ref "U$15") (pin "9") (pinfunction "BUFIN_9") (pintype "bidirectional"))
    )
    (net (code "63") (name "Net-(U$15-CAV)") (class "Default")
      (node (ref "C22") (pin "1") (pinfunction "1_1") (pintype "passive"))
      (node (ref "U$15") (pin "6") (pinfunction "CAV_6") (pintype "bidirectional"))
    )
    (net (code "64") (name "Net-(U$15-COM)") (class "Default")
      (node (ref "C20") (pin "1") (pinfunction "1_1") (pintype "passive"))
      (node (ref "R21") (pin "1") (pinfunction "1_1") (pintype "passive"))
      (node (ref "R22") (pin "2") (pinfunction "2_2") (pintype "passive"))
      (node (ref "U$15") (pin "2") (pinfunction "COM_2") (pintype "bidirectional"))
    )
    (net (code "65") (name "Net-(U$15-VIN)") (class "Default")
      (node (ref "C23") (pin "2") (pinfunction "2_2") (pintype "passive"))
      (node (ref "U$15") (pin "4") (pinfunction "VIN_4") (pintype "bidirectional"))
    )
    (net (code "66") (name "Net-(U$17-~{1})") (class "Default")
      (node (ref "U$16") (pin "OUT1") (pinfunction "OUT1_OUT1") (pintype "bidirectional"))
      (node (ref "U$17") (pin "~1") (pinfunction "~{1}_~1") (pintype "bidirectional"))
    )
    (net (code "67") (name "Net-(U$17-~{2})") (class "Default")
      (node (ref "U$16") (pin "OUT2") (pinfunction "OUT2_OUT2") (pintype "bidirectional"))
      (node (ref "U$17") (pin "~2") (pinfunction "~{2}_~2") (pintype "bidirectional"))
    )
    (net (code "68") (name "Net-(U$19-~{1})") (class "Default")
      (node (ref "U$18") (pin "OUT1") (pinfunction "OUT1_OUT1") (pintype "bidirectional"))
      (node (ref "U$19") (pin "~1") (pinfunction "~{1}_~1") (pintype "bidirectional"))
    )
    (net (code "69") (name "Net-(U$19-~{2})") (class "Default")
      (node (ref "U$18") (pin "OUT2") (pinfunction "OUT2_OUT2") (pintype "bidirectional"))
      (node (ref "U$19") (pin "~2") (pinfunction "~{2}_~2") (pintype "bidirectional"))
    )
    (net (code "70") (name "Net-(X2B-S)") (class "Default")
      (node (ref "R39") (pin "1") (pinfunction "1_1") (pintype "passive"))
      (node (ref "X2") (pin "2") (pinfunction "S_2") (pintype "passive"))
    )
    (net (code "71") (name "Net-(X3B-S)") (class "Default")
      (node (ref "R37") (pin "1") (pinfunction "1_1") (pintype "passive"))
      (node (ref "X3") (pin "2") (pinfunction "S_2") (pintype "passive"))
    )
    (net (code "72") (name "Net-(X4B-S)") (class "Default")
      (node (ref "R38") (pin "1") (pinfunction "1_1") (pintype "passive"))
      (node (ref "X4") (pin "2") (pinfunction "S_2") (pintype "passive"))
    )
    (net (code "73") (name "PE") (class "Default")
      (node (ref "U$20") (pin "PE") (pinfunction "PE_PE") (pintype "input"))
      (node (ref "X1") (pin "P$5") (pinfunction "P$5_P$5") (pintype "bidirectional"))
    )
    (net (code "74") (name "unconnected-(AC1002_1-3-PadP$3)") (class "Default")
      (node (ref "AC1002_1") (pin "P$3") (pinfunction "3_P$3") (pintype "no_connect"))
    )
    (net (code "75") (name "unconnected-(U$1-PadNC)") (class "Default")
      (node (ref "U$1") (pin "NC") (pinfunction "NC_NC") (pintype "bidirectional"))
    )
    (net (code "76") (name "unconnected-(U$1-PadNC1)") (class "Default")
      (node (ref "U$1") (pin "NC1") (pinfunction "NC1_NC1") (pintype "bidirectional"))
    )
    (net (code "77") (name "unconnected-(U$3-CLK-PadSCLOCK)") (class "Default")
      (node (ref "U$3") (pin "SCLOCK") (pinfunction "CLK_SCLOCK") (pintype "bidirectional"))
    )
    (net (code "78") (name "unconnected-(U$3-PadGND2)") (class "Default")
      (node (ref "U$3") (pin "GND2") (pinfunction "GND2_GND2") (pintype "bidirectional"))
    )
    (net (code "79") (name "unconnected-(U$3-PadGND3)") (class "Default")
      (node (ref "U$3") (pin "GND3") (pinfunction "GND3_GND3") (pintype "bidirectional"))
    )
    (net (code "80") (name "unconnected-(U$3-PadMISO)") (class "Default")
      (node (ref "U$3") (pin "MISO") (pinfunction "MISO_MISO") (pintype "bidirectional"))
    )
    (net (code "81") (name "unconnected-(U$3-PadMOSI)") (class "Default")
      (node (ref "U$3") (pin "MOSI") (pinfunction "MOSI_MOSI") (pintype "bidirectional"))
    )
    (net (code "82") (name "unconnected-(U$3-VCC2-PadVCC1)") (class "Default")
      (node (ref "U$3") (pin "VCC1") (pinfunction "VCC2_VCC1") (pintype "bidirectional"))
    )
    (net (code "83") (name "unconnected-(U$4-PadP$1)") (class "Default")
      (node (ref "U$4") (pin "P$1") (pinfunction "P$1_P$1") (pintype "bidirectional"))
    )
    (net (code "84") (name "unconnected-(U$4-PadP$6)") (class "Default")
      (node (ref "U$4") (pin "P$6") (pinfunction "P$6_P$6") (pintype "bidirectional"))
    )
    (net (code "85") (name "unconnected-(U$4-PadP$7)") (class "Default")
      (node (ref "U$4") (pin "P$7") (pinfunction "P$7_P$7") (pintype "bidirectional"))
    )
    (net (code "86") (name "unconnected-(U$4-PadP$8)") (class "Default")
      (node (ref "U$4") (pin "P$8") (pinfunction "P$8_P$8") (pintype "bidirectional"))
    )
    (net (code "87") (name "unconnected-(U$4-PadP$10)") (class "Default")
      (node (ref "U$4") (pin "P$10") (pinfunction "P$10_P$10") (pintype "bidirectional"))
    )
    (net (code "88") (name "unconnected-(U$4-PadP$11)") (class "Default")
      (node (ref "U$4") (pin "P$11") (pinfunction "P$11_P$11") (pintype "bidirectional"))
    )
    (net (code "89") (name "unconnected-(U$4-PadP$12)") (class "Default")
      (node (ref "U$4") (pin "P$12") (pinfunction "P$12_P$12") (pintype "bidirectional"))
    )
    (net (code "90") (name "unconnected-(U$4-PadP$13)") (class "Default")
      (node (ref "U$4") (pin "P$13") (pinfunction "P$13_P$13") (pintype "bidirectional"))
    )
    (net (code "91") (name "unconnected-(U$4-PadP$14)") (class "Default")
      (node (ref "U$4") (pin "P$14") (pinfunction "P$14_P$14") (pintype "bidirectional"))
    )
    (net (code "92") (name "unconnected-(U$4-PadP$15)") (class "Default")
      (node (ref "U$4") (pin "P$15") (pinfunction "P$15_P$15") (pintype "bidirectional"))
    )
    (net (code "93") (name "unconnected-(U$4-PadP$18)") (class "Default")
      (node (ref "U$4") (pin "P$18") (pinfunction "P$18_P$18") (pintype "bidirectional"))
    )
    (net (code "94") (name "unconnected-(U$4-PadP$19)") (class "Default")
      (node (ref "U$4") (pin "P$19") (pinfunction "P$19_P$19") (pintype "bidirectional"))
    )
    (net (code "95") (name "unconnected-(U$4-PadP$22)") (class "Default")
      (node (ref "U$4") (pin "P$22") (pinfunction "P$22_P$22") (pintype "bidirectional"))
    )
    (net (code "96") (name "unconnected-(U$4-PadP$23)") (class "Default")
      (node (ref "U$4") (pin "P$23") (pinfunction "P$23_P$23") (pintype "bidirectional"))
    )
    (net (code "97") (name "unconnected-(U$4-PadP$24)") (class "Default")
      (node (ref "U$4") (pin "P$24") (pinfunction "P$24_P$24") (pintype "bidirectional"))
    )
    (net (code "98") (name "unconnected-(U$4-PadP$26)") (class "Default")
      (node (ref "U$4") (pin "P$26") (pinfunction "P$26_P$26") (pintype "bidirectional"))
    )
    (net (code "99") (name "unconnected-(U$4-PadP$27)") (class "Default")
      (node (ref "U$4") (pin "P$27") (pinfunction "P$27_P$27") (pintype "bidirectional"))
    )
    (net (code "100") (name "unconnected-(U$4-PadP$28)") (class "Default")
      (node (ref "U$4") (pin "P$28") (pinfunction "P$28_P$28") (pintype "bidirectional"))
    )
    (net (code "101") (name "unconnected-(U$4-PadP$29)") (class "Default")
      (node (ref "U$4") (pin "P$29") (pinfunction "P$29_P$29") (pintype "bidirectional"))
    )
    (net (code "102") (name "unconnected-(U$4-PadP$30)") (class "Default")
      (node (ref "U$4") (pin "P$30") (pinfunction "P$30_P$30") (pintype "bidirectional"))
    )
    (net (code "103") (name "unconnected-(U$4-PadP$31)") (class "Default")
      (node (ref "U$4") (pin "P$31") (pinfunction "P$31_P$31") (pintype "bidirectional"))
    )
    (net (code "104") (name "unconnected-(U$7-3-PadP$3)") (class "Default")
      (node (ref "U$7") (pin "P$3") (pinfunction "3_P$3") (pintype "no_connect"))
    )
    (net (code "105") (name "unconnected-(U$12-DB-Pad7)") (class "Default")
      (node (ref "U$12") (pin "7") (pinfunction "DB_7") (pintype "bidirectional"))
    )
    (net (code "106") (name "unconnected-(U$13-DB-Pad7)") (class "Default")
      (node (ref "U$13") (pin "7") (pinfunction "DB_7") (pintype "bidirectional"))
    )
    (net (code "107") (name "unconnected-(U$14-3-PadP$3)") (class "Default")
      (node (ref "U$14") (pin "P$3") (pinfunction "3_P$3") (pintype "no_connect"))
    )
    (net (code "108") (name "unconnected-(U$15-DB-Pad7)") (class "Default")
      (node (ref "U$15") (pin "7") (pinfunction "DB_7") (pintype "bidirectional"))
    )
  )
)
